# untitled.net
KiCad netlist of a schematic drawn in EAGLE
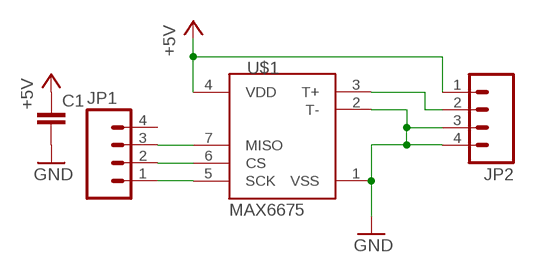
[diagram p0: schematic, sheet 1]

(export (version "E")
  (design (tool "Eeschema 10.0.6"))
  (components
    (comp (ref "C1")
      (value "CAP0805")
      (footprint "eagle-import:0805")
      (libsource (lib "eagle-import") (part "CAP0805"))
    )
    (comp (ref "JP1")
      (value "M04LONGPADS")
      (footprint "eagle-import:1X04_LONGPADS")
      (libsource (lib "eagle-import") (part "M04LONGPADS"))
    )
    (comp (ref "JP2")
      (value "M04LONGPADS")
      (footprint "eagle-import:1X04_LONGPADS")
      (libsource (lib "eagle-import") (part "M04LONGPADS"))
    )
    (comp (ref "U$1")
      (value "MAX6675")
      (footprint "eagle-import:SO08-MAX6675")
      (libsource (lib "eagle-import") (part "MAX6675"))
    )
  )
  (nets
    (net (code "1") (name "+5V") (class "Default")
      (node (ref "C1") (pin "1") (pinfunction "1_1") (pintype "passive"))
      (node (ref "JP2") (pin "1") (pinfunction "1_1") (pintype "passive"))
      (node (ref "U$1") (pin "4") (pinfunction "VDD_4") (pintype "bidirectional"))
    )
    (net (code "2") (name "GND") (class "Default")
      (node (ref "C1") (pin "2") (pinfunction "2_2") (pintype "passive"))
      (node (ref "JP2") (pin "3") (pinfunction "3_3") (pintype "passive"))
      (node (ref "JP2") (pin "4") (pinfunction "4_4") (pintype "passive"))
      (node (ref "U$1") (pin "1") (pinfunction "VSS_1") (pintype "bidirectional"))
      (node (ref "U$1") (pin "2") (pinfunction "T-_2") (pintype "bidirectional"))
    )
    (net (code "3") (name "Net-(U$1-CS)") (class "Default")
      (node (ref "JP1") (pin "2") (pinfunction "2_2") (pintype "passive"))
      (node (ref "U$1") (pin "6") (pinfunction "CS_6") (pintype "bidirectional"))
    )
    (net (code "4") (name "Net-(U$1-MISO)") (class "Default")
      (node (ref "JP1") (pin "3") (pinfunction "3_3") (pintype "passive"))
      (node (ref "U$1") (pin "7") (pinfunction "MISO_7") (pintype "bidirectional"))
    )
    (net (code "5") (name "Net-(U$1-SCK)") (class "Default")
      (node (ref "JP1") (pin "1") (pinfunction "1_1") (pintype "passive"))
      (node (ref "U$1") (pin "5") (pinfunction "SCK_5") (pintype "bidirectional"))
    )
    (net (code "6") (name "Net-(U$1-T+)") (class "Default")
      (node (ref "JP2") (pin "2") (pinfunction "2_2") (pintype "passive"))
      (node (ref "U$1") (pin "3") (pinfunction "T+_3") (pintype "bidirectional"))
    )
    (net (code "7") (name "unconnected-(JP1-Pad4)") (class "Default")
      (node (ref "JP1") (pin "4") (pinfunction "4_4") (pintype "passive"))
    )
  )
)
